# light.net
KiCad netlist of a schematic drawn in EAGLE
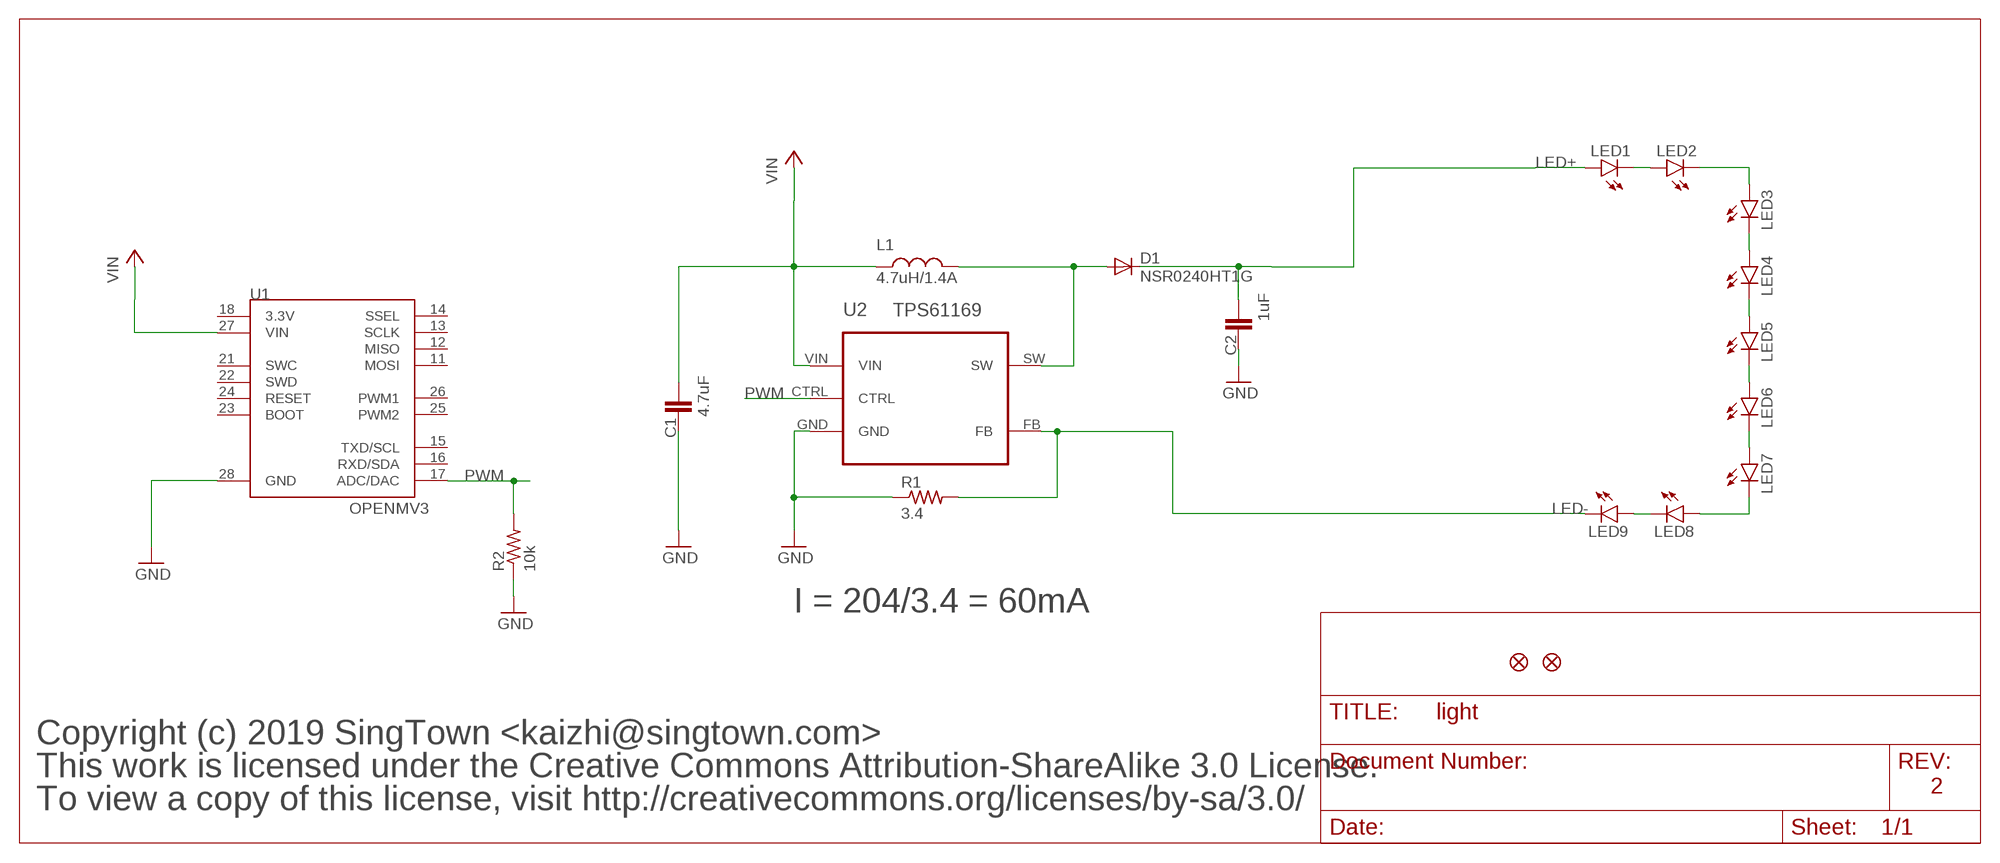
[diagram p0: schematic, sheet 1]

(export (version "E")
  (design (tool "Eeschema 10.0.6"))
  (components
    (comp (ref "C1")
      (value "4.7uF")
      (footprint "eagle-import:0603-CAP")
      (libsource (lib "eagle-import") (part "CAP0603-CAP"))
    )
    (comp (ref "C2")
      (value "1uF")
      (footprint "eagle-import:0603-CAP")
      (libsource (lib "eagle-import") (part "CAP0603-CAP"))
    )
    (comp (ref "D1")
      (value "NSR0240HT1G")
      (footprint "eagle-import:SOD-323")
      (libsource (lib "eagle-import") (part "DIODESOD"))
    )
    (comp (ref "L1")
      (value "4.7uH/1.4A")
      (footprint "eagle-import:1007")
      (libsource (lib "eagle-import") (part "INDUCTOR1007"))
    )
    (comp (ref "LED1")
      (value "LEDKA-3528ASYC")
      (footprint "eagle-import:KA-3528ASYC")
      (libsource (lib "eagle-import") (part "LEDKA-3528ASYC"))
    )
    (comp (ref "LED2")
      (value "LEDKA-3528ASYC")
      (footprint "eagle-import:KA-3528ASYC")
      (libsource (lib "eagle-import") (part "LEDKA-3528ASYC"))
    )
    (comp (ref "LED3")
      (value "LEDKA-3528ASYC")
      (footprint "eagle-import:KA-3528ASYC")
      (libsource (lib "eagle-import") (part "LEDKA-3528ASYC"))
    )
    (comp (ref "LED4")
      (value "LEDKA-3528ASYC")
      (footprint "eagle-import:KA-3528ASYC")
      (libsource (lib "eagle-import") (part "LEDKA-3528ASYC"))
    )
    (comp (ref "LED5")
      (value "LEDKA-3528ASYC")
      (footprint "eagle-import:KA-3528ASYC")
      (libsource (lib "eagle-import") (part "LEDKA-3528ASYC"))
    )
    (comp (ref "LED6")
      (value "LEDKA-3528ASYC")
      (footprint "eagle-import:KA-3528ASYC")
      (libsource (lib "eagle-import") (part "LEDKA-3528ASYC"))
    )
    (comp (ref "LED7")
      (value "LEDKA-3528ASYC")
      (footprint "eagle-import:KA-3528ASYC")
      (libsource (lib "eagle-import") (part "LEDKA-3528ASYC"))
    )
    (comp (ref "LED8")
      (value "LEDKA-3528ASYC")
      (footprint "eagle-import:KA-3528ASYC")
      (libsource (lib "eagle-import") (part "LEDKA-3528ASYC"))
    )
    (comp (ref "LED9")
      (value "LEDKA-3528ASYC")
      (footprint "eagle-import:KA-3528ASYC")
      (libsource (lib "eagle-import") (part "LEDKA-3528ASYC"))
    )
    (comp (ref "R1")
      (value "3.4")
      (footprint "eagle-import:R0603")
      (libsource (lib "eagle-import") (part "R-US_R0603"))
    )
    (comp (ref "R2")
      (value "10k")
      (footprint "eagle-import:R0603")
      (libsource (lib "eagle-import") (part "R-US_R0603"))
    )
    (comp (ref "U$4")
      (value "FIDUCIAL\"\"")
      (footprint "eagle-import:FIDUCIAL_1MM")
      (libsource (lib "eagle-import") (part "FIDUCIAL{dblquote}{dblquote}"))
    )
    (comp (ref "U$8")
      (value "FIDUCIAL\"\"")
      (footprint "eagle-import:FIDUCIAL_1MM")
      (libsource (lib "eagle-import") (part "FIDUCIAL{dblquote}{dblquote}"))
    )
    (comp (ref "U1")
      (value "OPENMV3")
      (footprint "eagle-import:OPENMV3")
      (libsource (lib "eagle-import") (part "OPENMV3"))
    )
    (comp (ref "U2")
      (value "TPS61169")
      (footprint "eagle-import:SOT65P210X110-5N")
      (fields (field (name "MPN") "74AHCT1G04GW/T1"))
      (libsource (lib "eagle-import") (part "74AHCT1G04GW/T1"))
    )
  )
  (nets
    (net (code "1") (name "/3.3V") (class "Default")
      (node (ref "U1") (pin "18") (pinfunction "3.3V_18") (pintype "power_in"))
    )
    (net (code "2") (name "/LED+") (class "Default")
      (node (ref "C2") (pin "1") (pinfunction "1_1") (pintype "passive"))
      (node (ref "D1") (pin "1") (pinfunction "C_1") (pintype "passive"))
      (node (ref "LED1") (pin "A") (pinfunction "A_A") (pintype "passive"))
    )
    (net (code "3") (name "/LED-") (class "Default")
      (node (ref "LED9") (pin "C") (pinfunction "C_C") (pintype "passive"))
      (node (ref "R1") (pin "2") (pinfunction "2_2") (pintype "passive"))
      (node (ref "U2") (pin "FB") (pinfunction "FB_FB") (pintype "input"))
    )
    (net (code "4") (name "/PWM") (class "Default")
      (node (ref "R2") (pin "2") (pinfunction "2_2") (pintype "passive"))
      (node (ref "U1") (pin "17") (pinfunction "ADC/DAC_17") (pintype "bidirectional"))
      (node (ref "U2") (pin "CTRL") (pinfunction "CTRL_CTRL") (pintype "input"))
    )
    (net (code "5") (name "GND") (class "Default")
      (node (ref "C1") (pin "2") (pinfunction "2_2") (pintype "passive"))
      (node (ref "C2") (pin "2") (pinfunction "2_2") (pintype "passive"))
      (node (ref "R1") (pin "1") (pinfunction "1_1") (pintype "passive"))
      (node (ref "R2") (pin "1") (pinfunction "1_1") (pintype "passive"))
      (node (ref "U1") (pin "28") (pinfunction "GND_28") (pintype "power_in"))
      (node (ref "U2") (pin "GND") (pinfunction "GND_GND") (pintype "power_in"))
    )
    (net (code "6") (name "Net-(D1-A)") (class "Default")
      (node (ref "D1") (pin "2") (pinfunction "A_2") (pintype "passive"))
      (node (ref "L1") (pin "2") (pinfunction "2_2") (pintype "passive"))
      (node (ref "U2") (pin "SW") (pinfunction "SW_SW") (pintype "output"))
    )
    (net (code "7") (name "Net-(LED1-PadC)") (class "Default")
      (node (ref "LED1") (pin "C") (pinfunction "C_C") (pintype "passive"))
      (node (ref "LED2") (pin "A") (pinfunction "A_A") (pintype "passive"))
    )
    (net (code "8") (name "Net-(LED2-PadC)") (class "Default")
      (node (ref "LED2") (pin "C") (pinfunction "C_C") (pintype "passive"))
      (node (ref "LED3") (pin "A") (pinfunction "A_A") (pintype "passive"))
    )
    (net (code "9") (name "Net-(LED3-PadC)") (class "Default")
      (node (ref "LED3") (pin "C") (pinfunction "C_C") (pintype "passive"))
      (node (ref "LED4") (pin "A") (pinfunction "A_A") (pintype "passive"))
    )
    (net (code "10") (name "Net-(LED4-PadC)") (class "Default")
      (node (ref "LED4") (pin "C") (pinfunction "C_C") (pintype "passive"))
      (node (ref "LED5") (pin "A") (pinfunction "A_A") (pintype "passive"))
    )
    (net (code "11") (name "Net-(LED5-PadC)") (class "Default")
      (node (ref "LED5") (pin "C") (pinfunction "C_C") (pintype "passive"))
      (node (ref "LED6") (pin "A") (pinfunction "A_A") (pintype "passive"))
    )
    (net (code "12") (name "Net-(LED6-PadC)") (class "Default")
      (node (ref "LED6") (pin "C") (pinfunction "C_C") (pintype "passive"))
      (node (ref "LED7") (pin "A") (pinfunction "A_A") (pintype "passive"))
    )
    (net (code "13") (name "Net-(LED7-PadC)") (class "Default")
      (node (ref "LED7") (pin "C") (pinfunction "C_C") (pintype "passive"))
      (node (ref "LED8") (pin "A") (pinfunction "A_A") (pintype "passive"))
    )
    (net (code "14") (name "Net-(LED8-PadC)") (class "Default")
      (node (ref "LED8") (pin "C") (pinfunction "C_C") (pintype "passive"))
      (node (ref "LED9") (pin "A") (pinfunction "A_A") (pintype "passive"))
    )
    (net (code "15") (name "VIN") (class "Default")
      (node (ref "C1") (pin "1") (pinfunction "1_1") (pintype "passive"))
      (node (ref "L1") (pin "1") (pinfunction "1_1") (pintype "passive"))
      (node (ref "U1") (pin "27") (pinfunction "VIN_27") (pintype "power_in"))
      (node (ref "U2") (pin "VIN") (pinfunction "VIN_VIN") (pintype "power_in"))
    )
    (net (code "16") (name "unconnected-(U1-BOOT-Pad23)") (class "Default")
      (node (ref "U1") (pin "23") (pinfunction "BOOT_23") (pintype "bidirectional"))
    )
    (net (code "17") (name "unconnected-(U1-MISO-Pad12)") (class "Default")
      (node (ref "U1") (pin "12") (pinfunction "MISO_12") (pintype "bidirectional"))
    )
    (net (code "18") (name "unconnected-(U1-MOSI-Pad11)") (class "Default")
      (node (ref "U1") (pin "11") (pinfunction "MOSI_11") (pintype "bidirectional"))
    )
    (net (code "19") (name "unconnected-(U1-PWM1-Pad26)") (class "Default")
      (node (ref "U1") (pin "26") (pinfunction "PWM1_26") (pintype "bidirectional"))
    )
    (net (code "20") (name "unconnected-(U1-PWM2-Pad25)") (class "Default")
      (node (ref "U1") (pin "25") (pinfunction "PWM2_25") (pintype "bidirectional"))
    )
    (net (code "21") (name "unconnected-(U1-RESET-Pad24)") (class "Default")
      (node (ref "U1") (pin "24") (pinfunction "RESET_24") (pintype "bidirectional"))
    )
    (net (code "22") (name "unconnected-(U1-RXD{slash}SDA-Pad16)") (class "Default")
      (node (ref "U1") (pin "16") (pinfunction "RXD/SDA_16") (pintype "bidirectional"))
    )
    (net (code "23") (name "unconnected-(U1-SCLK-Pad13)") (class "Default")
      (node (ref "U1") (pin "13") (pinfunction "SCLK_13") (pintype "bidirectional"))
    )
    (net (code "24") (name "unconnected-(U1-SSEL-Pad14)") (class "Default")
      (node (ref "U1") (pin "14") (pinfunction "SSEL_14") (pintype "bidirectional"))
    )
    (net (code "25") (name "unconnected-(U1-SWC-Pad21)") (class "Default")
      (node (ref "U1") (pin "21") (pinfunction "SWC_21") (pintype "bidirectional"))
    )
    (net (code "26") (name "unconnected-(U1-SWD-Pad22)") (class "Default")
      (node (ref "U1") (pin "22") (pinfunction "SWD_22") (pintype "bidirectional"))
    )
    (net (code "27") (name "unconnected-(U1-TXD{slash}SCL-Pad15)") (class "Default")
      (node (ref "U1") (pin "15") (pinfunction "TXD/SCL_15") (pintype "bidirectional"))
    )
  )
)
